# Hermes.net
KiCad netlist of a schematic drawn in Altium Designer
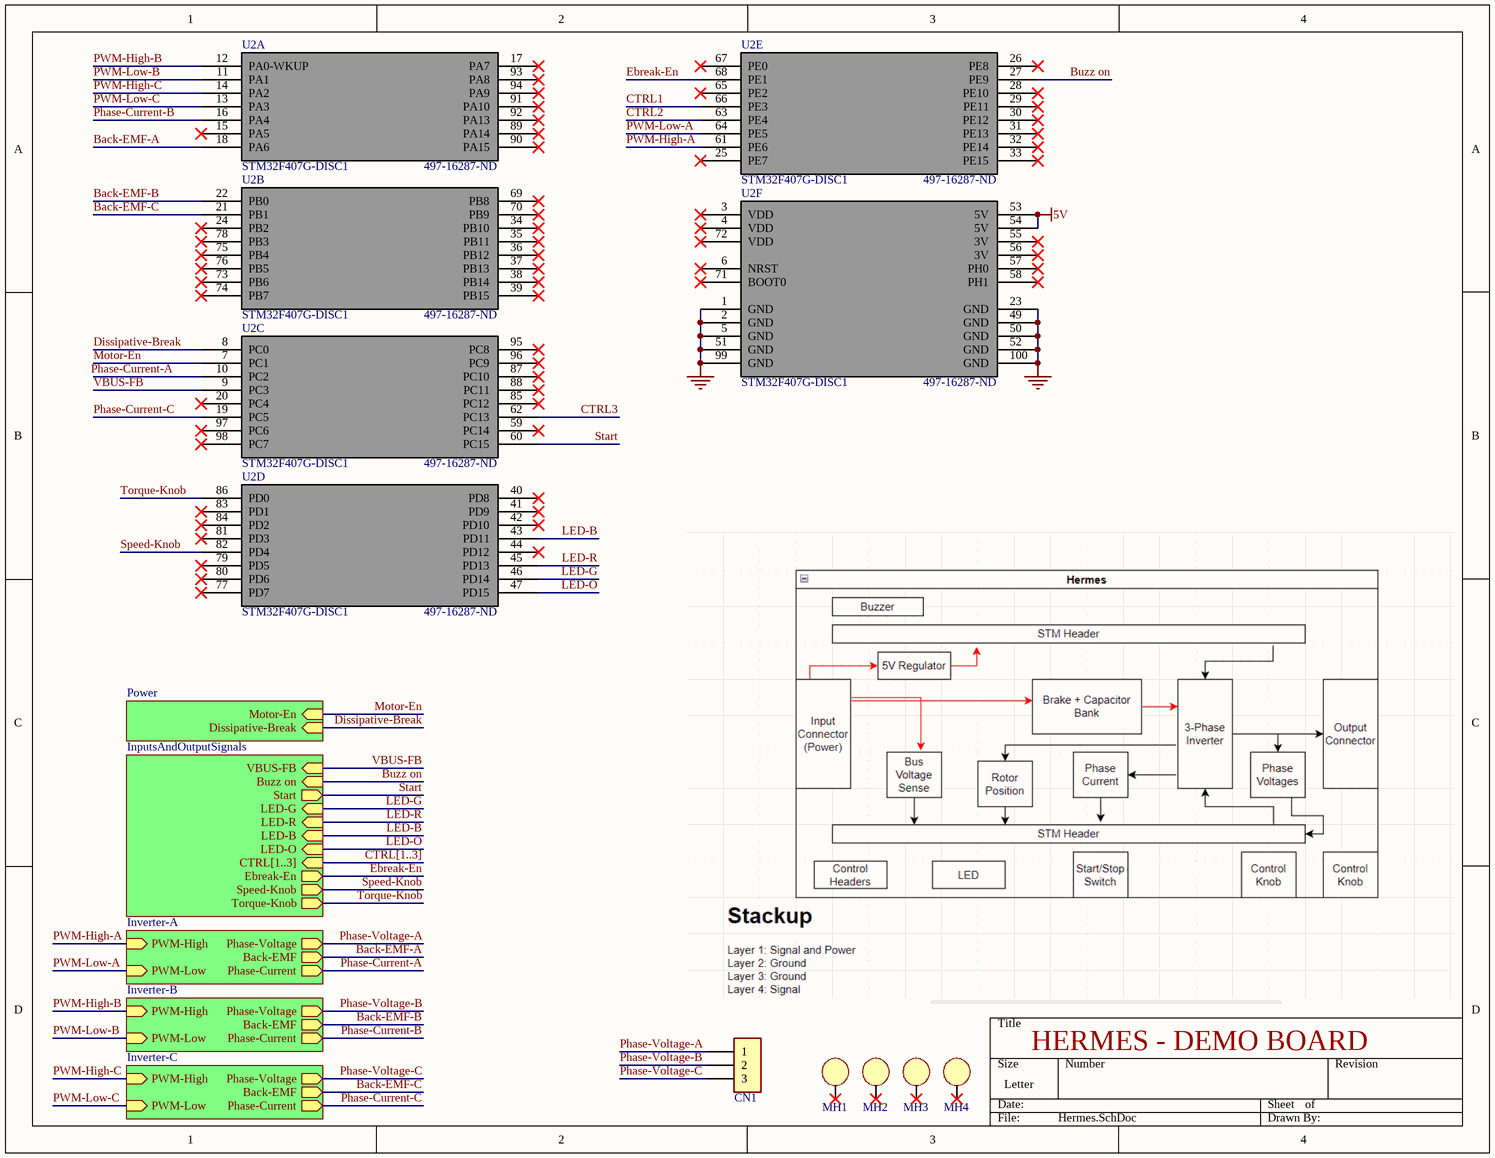
[diagram p0: Hermes.SchDoc]

(export (version "E")
  (design (tool "Eeschema 10.0.6"))
  (components
    (comp (ref "CN1")
      (value "Conn, 3-Pin")
      (footprint "Footprints:Conn, 3-Pin")
      (libsource (lib "499lib") (part "Conn, 3-Pin"))
    )
    (comp (ref "MH1")
      (value "Mount_Hole_3mm")
      (footprint "Mount-Hole_3mm")
      (description "Mounting hold for M3 hex standoff")
      (fields (field (name "SOURCE") "AUVic_Schematic_Library_Connectors.SchLib"))
      (libsource (lib "AUVIC") (part "Mount_Hole_3mm"))
    )
    (comp (ref "MH2")
      (value "Mount_Hole_3mm")
      (footprint "Mount-Hole_3mm")
      (description "Mounting hold for M3 hex standoff")
      (fields (field (name "SOURCE") "AUVic_Schematic_Library_Connectors.SchLib"))
      (libsource (lib "AUVIC") (part "Mount_Hole_3mm"))
    )
    (comp (ref "MH3")
      (value "Mount_Hole_3mm")
      (footprint "Mount-Hole_3mm")
      (description "Mounting hold for M3 hex standoff")
      (fields (field (name "SOURCE") "AUVic_Schematic_Library_Connectors.SchLib"))
      (libsource (lib "AUVIC") (part "Mount_Hole_3mm"))
    )
    (comp (ref "MH4")
      (value "Mount_Hole_3mm")
      (footprint "Mount-Hole_3mm")
      (description "Mounting hold for M3 hex standoff")
      (fields (field (name "SOURCE") "AUVic_Schematic_Library_Connectors.SchLib"))
      (libsource (lib "AUVIC") (part "Mount_Hole_3mm"))
    )
    (comp (ref "U2")
      (value "STM32F407G-DISC1")
      (footprint "Footprints:STM32F4")
      (fields (field (name "SUPPLIER PART NUMBER 1") "497-16287-ND"))
      (libsource (lib "499lib") (part "STM32F407G-DISC1"))
    )
  )
  (nets
    (net (code "1") (name "/Back-EMF-A") (class "Default")
      (node (ref "U2") (pin "18") (pinfunction "PA6_18") (pintype "passive"))
    )
    (net (code "2") (name "/Back-EMF-B") (class "Default")
      (node (ref "U2") (pin "22") (pinfunction "PB0_22") (pintype "passive"))
    )
    (net (code "3") (name "/Back-EMF-C") (class "Default")
      (node (ref "U2") (pin "21") (pinfunction "PB1_21") (pintype "passive"))
    )
    (net (code "4") (name "/Buzz on") (class "Default")
      (node (ref "U2") (pin "27") (pinfunction "PE9_27") (pintype "passive"))
    )
    (net (code "5") (name "/CTRL1") (class "Default")
      (node (ref "U2") (pin "66") (pinfunction "PE3_66") (pintype "passive"))
    )
    (net (code "6") (name "/CTRL2") (class "Default")
      (node (ref "U2") (pin "63") (pinfunction "PE4_63") (pintype "passive"))
    )
    (net (code "7") (name "/CTRL3") (class "Default")
      (node (ref "U2") (pin "62") (pinfunction "PC13_62") (pintype "passive"))
    )
    (net (code "9") (name "/Dissipative-Break") (class "Default")
      (node (ref "U2") (pin "8") (pinfunction "PC0_8") (pintype "passive"))
    )
    (net (code "10") (name "/Ebreak-En") (class "Default")
      (node (ref "U2") (pin "68") (pinfunction "PE1_68") (pintype "passive"))
    )
    (net (code "11") (name "/LED-B") (class "Default")
      (node (ref "U2") (pin "43") (pinfunction "PD11_43") (pintype "passive"))
    )
    (net (code "12") (name "/LED-G") (class "Default")
      (node (ref "U2") (pin "46") (pinfunction "PD14_46") (pintype "passive"))
    )
    (net (code "13") (name "/LED-O") (class "Default")
      (node (ref "U2") (pin "47") (pinfunction "PD15_47") (pintype "passive"))
    )
    (net (code "14") (name "/LED-R") (class "Default")
      (node (ref "U2") (pin "45") (pinfunction "PD13_45") (pintype "passive"))
    )
    (net (code "15") (name "/Motor-En") (class "Default")
      (node (ref "U2") (pin "7") (pinfunction "PC1_7") (pintype "passive"))
    )
    (net (code "16") (name "/PWM-High-A") (class "Default")
      (node (ref "U2") (pin "61") (pinfunction "PE6_61") (pintype "passive"))
    )
    (net (code "17") (name "/PWM-High-B") (class "Default")
      (node (ref "U2") (pin "12") (pinfunction "PA0-WKUP_12") (pintype "passive"))
    )
    (net (code "18") (name "/PWM-High-C") (class "Default")
      (node (ref "U2") (pin "14") (pinfunction "PA2_14") (pintype "passive"))
    )
    (net (code "19") (name "/PWM-Low-A") (class "Default")
      (node (ref "U2") (pin "64") (pinfunction "PE5_64") (pintype "passive"))
    )
    (net (code "20") (name "/PWM-Low-B") (class "Default")
      (node (ref "U2") (pin "11") (pinfunction "PA1_11") (pintype "passive"))
    )
    (net (code "21") (name "/PWM-Low-C") (class "Default")
      (node (ref "U2") (pin "13") (pinfunction "PA3_13") (pintype "passive"))
    )
    (net (code "22") (name "/Phase-Current-A") (class "Default")
      (node (ref "U2") (pin "10") (pinfunction "PC2_10") (pintype "passive"))
    )
    (net (code "23") (name "/Phase-Current-B") (class "Default")
      (node (ref "U2") (pin "16") (pinfunction "PA4_16") (pintype "passive"))
    )
    (net (code "24") (name "/Phase-Current-C") (class "Default")
      (node (ref "U2") (pin "19") (pinfunction "PC5_19") (pintype "passive"))
    )
    (net (code "25") (name "/Phase-Voltage-A") (class "Default")
      (node (ref "CN1") (pin "1") (pinfunction "1_1") (pintype "passive"))
    )
    (net (code "26") (name "/Phase-Voltage-B") (class "Default")
      (node (ref "CN1") (pin "2") (pinfunction "2_2") (pintype "passive"))
    )
    (net (code "27") (name "/Phase-Voltage-C") (class "Default")
      (node (ref "CN1") (pin "3") (pinfunction "3_3") (pintype "passive"))
    )
    (net (code "28") (name "/Speed-Knob") (class "Default")
      (node (ref "U2") (pin "82") (pinfunction "PD4_82") (pintype "passive"))
    )
    (net (code "29") (name "/Start") (class "Default")
      (node (ref "U2") (pin "60") (pinfunction "PC15_60") (pintype "passive"))
    )
    (net (code "30") (name "/Torque-Knob") (class "Default")
      (node (ref "U2") (pin "86") (pinfunction "PD0_86") (pintype "passive"))
    )
    (net (code "31") (name "/VBUS-FB") (class "Default")
      (node (ref "U2") (pin "9") (pinfunction "PC3_9") (pintype "passive"))
    )
    (net (code "32") (name "5V") (class "Default")
      (node (ref "U2") (pin "53") (pinfunction "5V_53") (pintype "passive"))
      (node (ref "U2") (pin "54") (pinfunction "5V_54") (pintype "passive"))
    )
    (net (code "33") (name "GND") (class "Default")
      (node (ref "U2") (pin "1") (pinfunction "GND_1") (pintype "passive"))
      (node (ref "U2") (pin "100") (pinfunction "GND_100") (pintype "passive"))
      (node (ref "U2") (pin "2") (pinfunction "GND_2") (pintype "passive"))
      (node (ref "U2") (pin "23") (pinfunction "GND_23") (pintype "passive"))
      (node (ref "U2") (pin "49") (pinfunction "GND_49") (pintype "passive"))
      (node (ref "U2") (pin "5") (pinfunction "GND_5") (pintype "passive"))
      (node (ref "U2") (pin "50") (pinfunction "GND_50") (pintype "passive"))
      (node (ref "U2") (pin "51") (pinfunction "GND_51") (pintype "passive"))
      (node (ref "U2") (pin "52") (pinfunction "GND_52") (pintype "passive"))
      (node (ref "U2") (pin "99") (pinfunction "GND_99") (pintype "passive"))
    )
    (net (code "34") (name "unconnected-(MH1-Pad1)") (class "Default")
      (node (ref "MH1") (pin "1") (pinfunction "1_1") (pintype "passive+no_connect"))
    )
    (net (code "35") (name "unconnected-(MH2-Pad1)") (class "Default")
      (node (ref "MH2") (pin "1") (pinfunction "1_1") (pintype "passive+no_connect"))
    )
    (net (code "36") (name "unconnected-(MH3-Pad1)") (class "Default")
      (node (ref "MH3") (pin "1") (pinfunction "1_1") (pintype "passive+no_connect"))
    )
    (net (code "37") (name "unconnected-(MH4-Pad1)") (class "Default")
      (node (ref "MH4") (pin "1") (pinfunction "1_1") (pintype "passive+no_connect"))
    )
    (net (code "38") (name "unconnected-(U2A-PA5-Pad15)") (class "Default")
      (node (ref "U2") (pin "15") (pinfunction "PA5_15") (pintype "passive+no_connect"))
    )
    (net (code "39") (name "unconnected-(U2A-PA7-Pad17)") (class "Default")
      (node (ref "U2") (pin "17") (pinfunction "PA7_17") (pintype "passive+no_connect"))
    )
    (net (code "40") (name "unconnected-(U2A-PA8-Pad93)") (class "Default")
      (node (ref "U2") (pin "93") (pinfunction "PA8_93") (pintype "passive+no_connect"))
    )
    (net (code "41") (name "unconnected-(U2A-PA9-Pad94)") (class "Default")
      (node (ref "U2") (pin "94") (pinfunction "PA9_94") (pintype "passive+no_connect"))
    )
    (net (code "42") (name "unconnected-(U2A-PA10-Pad91)") (class "Default")
      (node (ref "U2") (pin "91") (pinfunction "PA10_91") (pintype "passive+no_connect"))
    )
    (net (code "43") (name "unconnected-(U2A-PA13-Pad92)") (class "Default")
      (node (ref "U2") (pin "92") (pinfunction "PA13_92") (pintype "passive+no_connect"))
    )
    (net (code "44") (name "unconnected-(U2A-PA14-Pad89)") (class "Default")
      (node (ref "U2") (pin "89") (pinfunction "PA14_89") (pintype "passive+no_connect"))
    )
    (net (code "45") (name "unconnected-(U2A-PA15-Pad90)") (class "Default")
      (node (ref "U2") (pin "90") (pinfunction "PA15_90") (pintype "passive+no_connect"))
    )
    (net (code "46") (name "unconnected-(U2B-PB2-Pad24)") (class "Default")
      (node (ref "U2") (pin "24") (pinfunction "PB2_24") (pintype "passive+no_connect"))
    )
    (net (code "47") (name "unconnected-(U2B-PB3-Pad78)") (class "Default")
      (node (ref "U2") (pin "78") (pinfunction "PB3_78") (pintype "passive+no_connect"))
    )
    (net (code "48") (name "unconnected-(U2B-PB4-Pad75)") (class "Default")
      (node (ref "U2") (pin "75") (pinfunction "PB4_75") (pintype "passive+no_connect"))
    )
    (net (code "49") (name "unconnected-(U2B-PB5-Pad76)") (class "Default")
      (node (ref "U2") (pin "76") (pinfunction "PB5_76") (pintype "passive+no_connect"))
    )
    (net (code "50") (name "unconnected-(U2B-PB6-Pad73)") (class "Default")
      (node (ref "U2") (pin "73") (pinfunction "PB6_73") (pintype "passive+no_connect"))
    )
    (net (code "51") (name "unconnected-(U2B-PB7-Pad74)") (class "Default")
      (node (ref "U2") (pin "74") (pinfunction "PB7_74") (pintype "passive+no_connect"))
    )
    (net (code "52") (name "unconnected-(U2B-PB8-Pad69)") (class "Default")
      (node (ref "U2") (pin "69") (pinfunction "PB8_69") (pintype "passive+no_connect"))
    )
    (net (code "53") (name "unconnected-(U2B-PB9-Pad70)") (class "Default")
      (node (ref "U2") (pin "70") (pinfunction "PB9_70") (pintype "passive+no_connect"))
    )
    (net (code "54") (name "unconnected-(U2B-PB10-Pad34)") (class "Default")
      (node (ref "U2") (pin "34") (pinfunction "PB10_34") (pintype "passive+no_connect"))
    )
    (net (code "55") (name "unconnected-(U2B-PB11-Pad35)") (class "Default")
      (node (ref "U2") (pin "35") (pinfunction "PB11_35") (pintype "passive+no_connect"))
    )
    (net (code "56") (name "unconnected-(U2B-PB12-Pad36)") (class "Default")
      (node (ref "U2") (pin "36") (pinfunction "PB12_36") (pintype "passive+no_connect"))
    )
    (net (code "57") (name "unconnected-(U2B-PB13-Pad37)") (class "Default")
      (node (ref "U2") (pin "37") (pinfunction "PB13_37") (pintype "passive+no_connect"))
    )
    (net (code "58") (name "unconnected-(U2B-PB14-Pad38)") (class "Default")
      (node (ref "U2") (pin "38") (pinfunction "PB14_38") (pintype "passive+no_connect"))
    )
    (net (code "59") (name "unconnected-(U2B-PB15-Pad39)") (class "Default")
      (node (ref "U2") (pin "39") (pinfunction "PB15_39") (pintype "passive+no_connect"))
    )
    (net (code "60") (name "unconnected-(U2C-PC4-Pad20)") (class "Default")
      (node (ref "U2") (pin "20") (pinfunction "PC4_20") (pintype "passive+no_connect"))
    )
    (net (code "61") (name "unconnected-(U2C-PC6-Pad97)") (class "Default")
      (node (ref "U2") (pin "97") (pinfunction "PC6_97") (pintype "passive+no_connect"))
    )
    (net (code "62") (name "unconnected-(U2C-PC7-Pad98)") (class "Default")
      (node (ref "U2") (pin "98") (pinfunction "PC7_98") (pintype "passive+no_connect"))
    )
    (net (code "63") (name "unconnected-(U2C-PC8-Pad95)") (class "Default")
      (node (ref "U2") (pin "95") (pinfunction "PC8_95") (pintype "passive+no_connect"))
    )
    (net (code "64") (name "unconnected-(U2C-PC9-Pad96)") (class "Default")
      (node (ref "U2") (pin "96") (pinfunction "PC9_96") (pintype "passive+no_connect"))
    )
    (net (code "65") (name "unconnected-(U2C-PC10-Pad87)") (class "Default")
      (node (ref "U2") (pin "87") (pinfunction "PC10_87") (pintype "passive+no_connect"))
    )
    (net (code "66") (name "unconnected-(U2C-PC11-Pad88)") (class "Default")
      (node (ref "U2") (pin "88") (pinfunction "PC11_88") (pintype "passive+no_connect"))
    )
    (net (code "67") (name "unconnected-(U2C-PC12-Pad85)") (class "Default")
      (node (ref "U2") (pin "85") (pinfunction "PC12_85") (pintype "passive+no_connect"))
    )
    (net (code "68") (name "unconnected-(U2C-PC14-Pad59)") (class "Default")
      (node (ref "U2") (pin "59") (pinfunction "PC14_59") (pintype "passive+no_connect"))
    )
    (net (code "69") (name "unconnected-(U2D-PD1-Pad83)") (class "Default")
      (node (ref "U2") (pin "83") (pinfunction "PD1_83") (pintype "passive+no_connect"))
    )
    (net (code "70") (name "unconnected-(U2D-PD2-Pad84)") (class "Default")
      (node (ref "U2") (pin "84") (pinfunction "PD2_84") (pintype "passive+no_connect"))
    )
    (net (code "71") (name "unconnected-(U2D-PD3-Pad81)") (class "Default")
      (node (ref "U2") (pin "81") (pinfunction "PD3_81") (pintype "passive+no_connect"))
    )
    (net (code "72") (name "unconnected-(U2D-PD5-Pad79)") (class "Default")
      (node (ref "U2") (pin "79") (pinfunction "PD5_79") (pintype "passive+no_connect"))
    )
    (net (code "73") (name "unconnected-(U2D-PD6-Pad80)") (class "Default")
      (node (ref "U2") (pin "80") (pinfunction "PD6_80") (pintype "passive+no_connect"))
    )
    (net (code "74") (name "unconnected-(U2D-PD7-Pad77)") (class "Default")
      (node (ref "U2") (pin "77") (pinfunction "PD7_77") (pintype "passive+no_connect"))
    )
    (net (code "75") (name "unconnected-(U2D-PD8-Pad40)") (class "Default")
      (node (ref "U2") (pin "40") (pinfunction "PD8_40") (pintype "passive+no_connect"))
    )
    (net (code "76") (name "unconnected-(U2D-PD9-Pad41)") (class "Default")
      (node (ref "U2") (pin "41") (pinfunction "PD9_41") (pintype "passive+no_connect"))
    )
    (net (code "77") (name "unconnected-(U2D-PD10-Pad42)") (class "Default")
      (node (ref "U2") (pin "42") (pinfunction "PD10_42") (pintype "passive+no_connect"))
    )
    (net (code "78") (name "unconnected-(U2D-PD12-Pad44)") (class "Default")
      (node (ref "U2") (pin "44") (pinfunction "PD12_44") (pintype "passive+no_connect"))
    )
    (net (code "79") (name "unconnected-(U2E-PE0-Pad67)") (class "Default")
      (node (ref "U2") (pin "67") (pinfunction "PE0_67") (pintype "passive+no_connect"))
    )
    (net (code "80") (name "unconnected-(U2E-PE2-Pad65)") (class "Default")
      (node (ref "U2") (pin "65") (pinfunction "PE2_65") (pintype "passive+no_connect"))
    )
    (net (code "81") (name "unconnected-(U2E-PE7-Pad25)") (class "Default")
      (node (ref "U2") (pin "25") (pinfunction "PE7_25") (pintype "passive+no_connect"))
    )
    (net (code "82") (name "unconnected-(U2E-PE8-Pad26)") (class "Default")
      (node (ref "U2") (pin "26") (pinfunction "PE8_26") (pintype "passive+no_connect"))
    )
    (net (code "83") (name "unconnected-(U2E-PE10-Pad28)") (class "Default")
      (node (ref "U2") (pin "28") (pinfunction "PE10_28") (pintype "passive+no_connect"))
    )
    (net (code "84") (name "unconnected-(U2E-PE11-Pad29)") (class "Default")
      (node (ref "U2") (pin "29") (pinfunction "PE11_29") (pintype "passive+no_connect"))
    )
    (net (code "85") (name "unconnected-(U2E-PE12-Pad30)") (class "Default")
      (node (ref "U2") (pin "30") (pinfunction "PE12_30") (pintype "passive+no_connect"))
    )
    (net (code "86") (name "unconnected-(U2E-PE13-Pad31)") (class "Default")
      (node (ref "U2") (pin "31") (pinfunction "PE13_31") (pintype "passive+no_connect"))
    )
    (net (code "87") (name "unconnected-(U2E-PE14-Pad32)") (class "Default")
      (node (ref "U2") (pin "32") (pinfunction "PE14_32") (pintype "passive+no_connect"))
    )
    (net (code "88") (name "unconnected-(U2E-PE15-Pad33)") (class "Default")
      (node (ref "U2") (pin "33") (pinfunction "PE15_33") (pintype "passive+no_connect"))
    )
    (net (code "89") (name "unconnected-(U2F-3V-Pad55)") (class "Default")
      (node (ref "U2") (pin "55") (pinfunction "3V_55") (pintype "passive+no_connect"))
    )
    (net (code "90") (name "unconnected-(U2F-3V-Pad56)") (class "Default")
      (node (ref "U2") (pin "56") (pinfunction "3V_56") (pintype "passive+no_connect"))
    )
    (net (code "91") (name "unconnected-(U2F-BOOT0-Pad71)") (class "Default")
      (node (ref "U2") (pin "71") (pinfunction "BOOT0_71") (pintype "passive+no_connect"))
    )
    (net (code "92") (name "unconnected-(U2F-NRST-Pad6)") (class "Default")
      (node (ref "U2") (pin "6") (pinfunction "NRST_6") (pintype "passive+no_connect"))
    )
    (net (code "93") (name "unconnected-(U2F-PH0-Pad57)") (class "Default")
      (node (ref "U2") (pin "57") (pinfunction "PH0_57") (pintype "passive+no_connect"))
    )
    (net (code "94") (name "unconnected-(U2F-PH1-Pad58)") (class "Default")
      (node (ref "U2") (pin "58") (pinfunction "PH1_58") (pintype "passive+no_connect"))
    )
    (net (code "95") (name "unconnected-(U2F-VDD-Pad3)") (class "Default")
      (node (ref "U2") (pin "3") (pinfunction "VDD_3") (pintype "passive+no_connect"))
    )
    (net (code "96") (name "unconnected-(U2F-VDD-Pad4)") (class "Default")
      (node (ref "U2") (pin "4") (pinfunction "VDD_4") (pintype "passive+no_connect"))
    )
    (net (code "97") (name "unconnected-(U2F-VDD-Pad72)") (class "Default")
      (node (ref "U2") (pin "72") (pinfunction "VDD_72") (pintype "passive+no_connect"))
    )
  )
)
